# AnalogI_3_3V_LevelShift.net
KiCad netlist of a schematic drawn in EAGLE
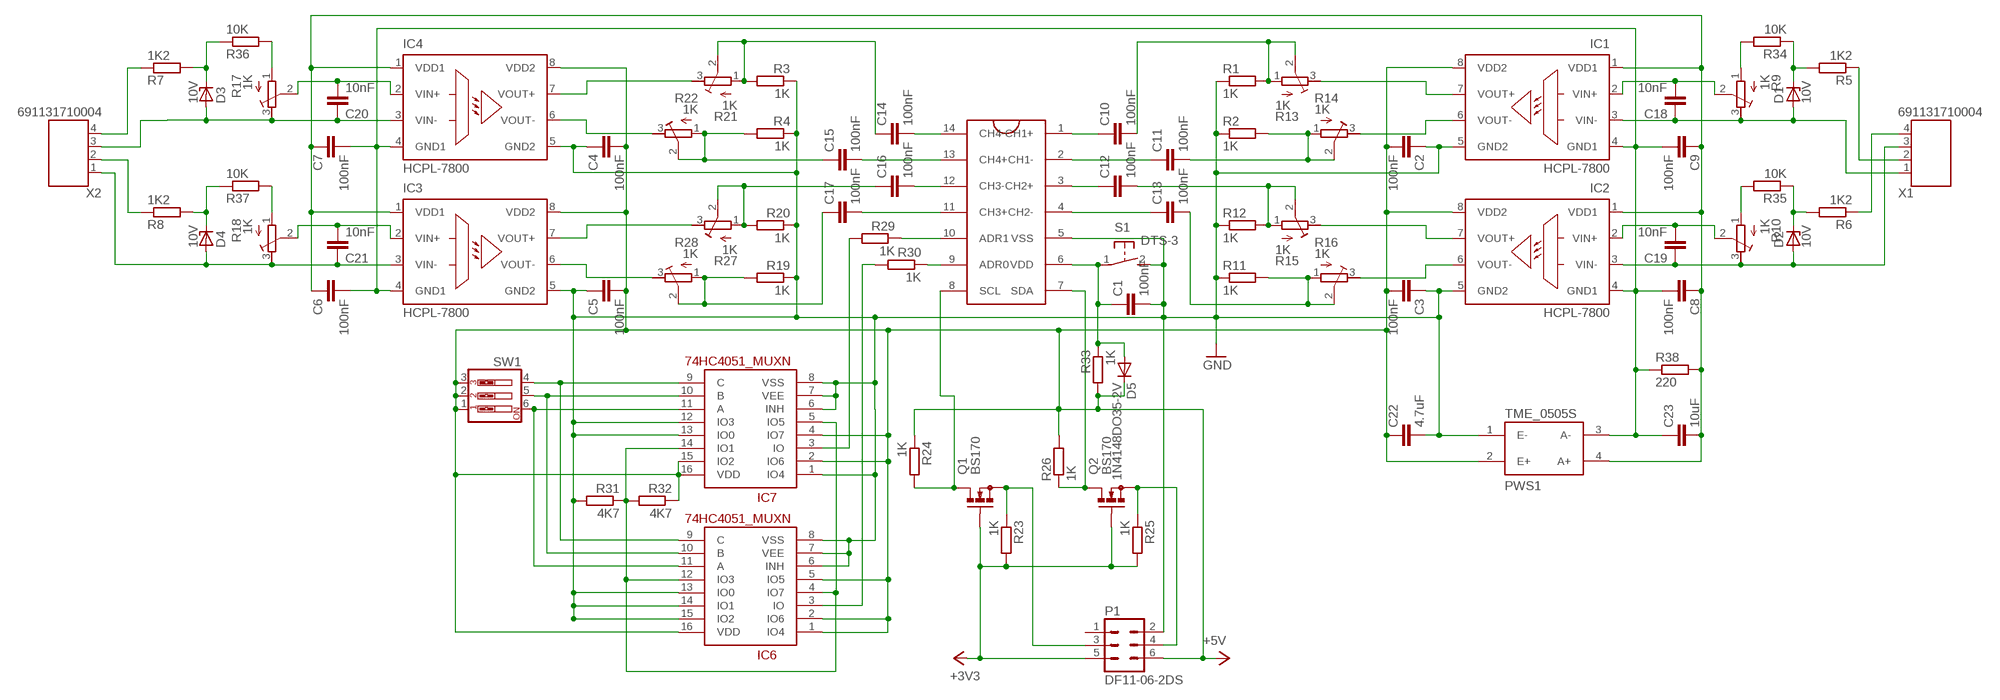
[diagram p0: schematic, sheet 1]

(export (version "E")
  (design (tool "Eeschema 10.0.6"))
  (components
    (comp (ref "C1")
      (value "100nF")
      (footprint "eagle-import:C025-024X044")
      (libsource (lib "eagle-import") (part "C-EU025-024X044"))
    )
    (comp (ref "C2")
      (value "100nF")
      (footprint "eagle-import:C025-024X044")
      (libsource (lib "eagle-import") (part "C-EU025-024X044"))
    )
    (comp (ref "C3")
      (value "100nF")
      (footprint "eagle-import:C025-024X044")
      (libsource (lib "eagle-import") (part "C-EU025-024X044"))
    )
    (comp (ref "C4")
      (value "100nF")
      (footprint "eagle-import:C025-024X044")
      (libsource (lib "eagle-import") (part "C-EU025-024X044"))
    )
    (comp (ref "C5")
      (value "100nF")
      (footprint "eagle-import:C025-024X044")
      (libsource (lib "eagle-import") (part "C-EU025-024X044"))
    )
    (comp (ref "C6")
      (value "100nF")
      (footprint "eagle-import:C025-024X044")
      (libsource (lib "eagle-import") (part "C-EU025-024X044"))
    )
    (comp (ref "C7")
      (value "100nF")
      (footprint "eagle-import:C025-024X044")
      (libsource (lib "eagle-import") (part "C-EU025-024X044"))
    )
    (comp (ref "C8")
      (value "100nF")
      (footprint "eagle-import:C025-024X044")
      (libsource (lib "eagle-import") (part "C-EU025-024X044"))
    )
    (comp (ref "C9")
      (value "100nF")
      (footprint "eagle-import:C025-024X044")
      (libsource (lib "eagle-import") (part "C-EU025-024X044"))
    )
    (comp (ref "C10")
      (value "100nF")
      (footprint "eagle-import:C5B3")
      (libsource (lib "eagle-import") (part "C5/3"))
    )
    (comp (ref "C11")
      (value "100nF")
      (footprint "eagle-import:C5B3")
      (libsource (lib "eagle-import") (part "C5/3"))
    )
    (comp (ref "C12")
      (value "100nF")
      (footprint "eagle-import:C5B3")
      (libsource (lib "eagle-import") (part "C5/3"))
    )
    (comp (ref "C13")
      (value "100nF")
      (footprint "eagle-import:C5B3")
      (libsource (lib "eagle-import") (part "C5/3"))
    )
    (comp (ref "C14")
      (value "100nF")
      (footprint "eagle-import:C5B3")
      (libsource (lib "eagle-import") (part "C5/3"))
    )
    (comp (ref "C15")
      (value "100nF")
      (footprint "eagle-import:C5B3")
      (libsource (lib "eagle-import") (part "C5/3"))
    )
    (comp (ref "C16")
      (value "100nF")
      (footprint "eagle-import:C5B3")
      (libsource (lib "eagle-import") (part "C5/3"))
    )
    (comp (ref "C17")
      (value "100nF")
      (footprint "eagle-import:C5B3")
      (libsource (lib "eagle-import") (part "C5/3"))
    )
    (comp (ref "C18")
      (value "10nF")
      (footprint "eagle-import:C2.5-3")
      (libsource (lib "eagle-import") (part "C2,5-3"))
    )
    (comp (ref "C19")
      (value "10nF")
      (footprint "eagle-import:C2.5-3")
      (libsource (lib "eagle-import") (part "C2,5-3"))
    )
    (comp (ref "C20")
      (value "10nF")
      (footprint "eagle-import:C2.5-3")
      (libsource (lib "eagle-import") (part "C2,5-3"))
    )
    (comp (ref "C21")
      (value "10nF")
      (footprint "eagle-import:C2.5-3")
      (libsource (lib "eagle-import") (part "C2,5-3"))
    )
    (comp (ref "C22")
      (value "4.7uF")
      (footprint "eagle-import:C0805")
      (libsource (lib "eagle-import") (part "C-EUC0805"))
    )
    (comp (ref "C23")
      (value "10uF")
      (footprint "eagle-import:C0805")
      (libsource (lib "eagle-import") (part "C-EUC0805"))
    )
    (comp (ref "D1")
      (value "10V")
      (footprint "eagle-import:ZDIO-2.5")
      (libsource (lib "eagle-import") (part "ZENER-DIODEZD-2.5"))
    )
    (comp (ref "D2")
      (value "10V")
      (footprint "eagle-import:ZDIO-2.5")
      (libsource (lib "eagle-import") (part "ZENER-DIODEZD-2.5"))
    )
    (comp (ref "D3")
      (value "10V")
      (footprint "eagle-import:ZDIO-2.5")
      (libsource (lib "eagle-import") (part "ZENER-DIODEZD-2.5"))
    )
    (comp (ref "D4")
      (value "10V")
      (footprint "eagle-import:ZDIO-2.5")
      (libsource (lib "eagle-import") (part "ZENER-DIODEZD-2.5"))
    )
    (comp (ref "D5")
      (value "1N4148DO35-2V")
      (footprint "eagle-import:DO35-2V")
      (libsource (lib "eagle-import") (part "1N4148DO35-2V"))
    )
    (comp (ref "IC1")
      (value "HCPL-7800")
      (footprint "eagle-import:DIL08")
      (fields (field (name "MPN") "HCPL-7800A#500"))
      (libsource (lib "eagle-import") (part "HCPL-7800"))
    )
    (comp (ref "IC2")
      (value "HCPL-7800")
      (footprint "eagle-import:DIL08")
      (fields (field (name "MPN") "HCPL-7800A#500"))
      (libsource (lib "eagle-import") (part "HCPL-7800"))
    )
    (comp (ref "IC3")
      (value "HCPL-7800")
      (footprint "eagle-import:DIL08")
      (fields (field (name "MPN") "HCPL-7800A#500"))
      (libsource (lib "eagle-import") (part "HCPL-7800"))
    )
    (comp (ref "IC4")
      (value "HCPL-7800")
      (footprint "eagle-import:DIL08")
      (fields (field (name "MPN") "HCPL-7800A#500"))
      (libsource (lib "eagle-import") (part "HCPL-7800"))
    )
    (comp (ref "IC5")
      (value "MCP3424SOIC")
      (footprint "eagle-import:14LDSOIC")
      (libsource (lib "eagle-import") (part "MCP3424SOIC"))
    )
    (comp (ref "IC6")
      (value "74HC4051_MUXN")
      (footprint "eagle-import:DIL16")
      (libsource (lib "eagle-import") (part "74HC4051_MUXN"))
    )
    (comp (ref "IC7")
      (value "74HC4051_MUXN")
      (footprint "eagle-import:DIL16")
      (libsource (lib "eagle-import") (part "74HC4051_MUXN"))
    )
    (comp (ref "P1")
      (value "DF11-06-2DS")
      (footprint "eagle-import:DF11-06DP-2DS")
      (libsource (lib "eagle-import") (part "DF11-06-2DS"))
    )
    (comp (ref "PWS1")
      (value "TME_0505S")
      (footprint "eagle-import:TMEXXXXS")
      (fields (field (name "MPN") "TME 0505S"))
      (libsource (lib "eagle-import") (part "TME_S0505"))
    )
    (comp (ref "Q1")
      (value "BS170")
      (footprint "eagle-import:SOT54E")
      (fields (field (name "MF") "ON SEMICONDUCTOR") (field (name "MPN") "BS170G"))
      (libsource (lib "eagle-import") (part "BS170"))
    )
    (comp (ref "Q2")
      (value "BS170")
      (footprint "eagle-import:SOT54E")
      (fields (field (name "MF") "ON SEMICONDUCTOR") (field (name "MPN") "BS170G"))
      (libsource (lib "eagle-import") (part "BS170"))
    )
    (comp (ref "R1")
      (value "1K")
      (footprint "eagle-import:0204V")
      (libsource (lib "eagle-import") (part "R-EU_0204/2V"))
    )
    (comp (ref "R2")
      (value "1K")
      (footprint "eagle-import:0204V")
      (libsource (lib "eagle-import") (part "R-EU_0204/2V"))
    )
    (comp (ref "R3")
      (value "1K")
      (footprint "eagle-import:0204V")
      (libsource (lib "eagle-import") (part "R-EU_0204/2V"))
    )
    (comp (ref "R4")
      (value "1K")
      (footprint "eagle-import:0204V")
      (libsource (lib "eagle-import") (part "R-EU_0204/2V"))
    )
    (comp (ref "R5")
      (value "1K2")
      (footprint "eagle-import:0204V")
      (libsource (lib "eagle-import") (part "R-EU_0204/2V"))
    )
    (comp (ref "R6")
      (value "1K2")
      (footprint "eagle-import:0204V")
      (libsource (lib "eagle-import") (part "R-EU_0204/2V"))
    )
    (comp (ref "R7")
      (value "1K2")
      (footprint "eagle-import:0204V")
      (libsource (lib "eagle-import") (part "R-EU_0204/2V"))
    )
    (comp (ref "R8")
      (value "1K2")
      (footprint "eagle-import:0204V")
      (libsource (lib "eagle-import") (part "R-EU_0204/2V"))
    )
    (comp (ref "R9")
      (value "1K")
      (footprint "eagle-import:RTRIM3296W")
      (libsource (lib "eagle-import") (part "R-TRIMM3296W"))
    )
    (comp (ref "R10")
      (value "1K")
      (footprint "eagle-import:RTRIM3296W")
      (libsource (lib "eagle-import") (part "R-TRIMM3296W"))
    )
    (comp (ref "R11")
      (value "1K")
      (footprint "eagle-import:0204V")
      (libsource (lib "eagle-import") (part "R-EU_0204/2V"))
    )
    (comp (ref "R12")
      (value "1K")
      (footprint "eagle-import:0204V")
      (libsource (lib "eagle-import") (part "R-EU_0204/2V"))
    )
    (comp (ref "R13")
      (value "1K")
      (footprint "eagle-import:RTRIM3296W")
      (libsource (lib "eagle-import") (part "R-TRIMM3296W"))
    )
    (comp (ref "R14")
      (value "1K")
      (footprint "eagle-import:RTRIM3296W")
      (libsource (lib "eagle-import") (part "R-TRIMM3296W"))
    )
    (comp (ref "R15")
      (value "1K")
      (footprint "eagle-import:RTRIM3296W")
      (libsource (lib "eagle-import") (part "R-TRIMM3296W"))
    )
    (comp (ref "R16")
      (value "1K")
      (footprint "eagle-import:RTRIM3296W")
      (libsource (lib "eagle-import") (part "R-TRIMM3296W"))
    )
    (comp (ref "R17")
      (value "1K")
      (footprint "eagle-import:RTRIM3296W")
      (libsource (lib "eagle-import") (part "R-TRIMM3296W"))
    )
    (comp (ref "R18")
      (value "1K")
      (footprint "eagle-import:RTRIM3296W")
      (libsource (lib "eagle-import") (part "R-TRIMM3296W"))
    )
    (comp (ref "R19")
      (value "1K")
      (footprint "eagle-import:0204V")
      (libsource (lib "eagle-import") (part "R-EU_0204/2V"))
    )
    (comp (ref "R20")
      (value "1K")
      (footprint "eagle-import:0204V")
      (libsource (lib "eagle-import") (part "R-EU_0204/2V"))
    )
    (comp (ref "R21")
      (value "1K")
      (footprint "eagle-import:RTRIM3296W")
      (libsource (lib "eagle-import") (part "R-TRIMM3296W"))
    )
    (comp (ref "R22")
      (value "1K")
      (footprint "eagle-import:RTRIM3296W")
      (libsource (lib "eagle-import") (part "R-TRIMM3296W"))
    )
    (comp (ref "R23")
      (value "1K")
      (footprint "eagle-import:0204V")
      (libsource (lib "eagle-import") (part "R-EU_0204/2V"))
    )
    (comp (ref "R24")
      (value "1K")
      (footprint "eagle-import:0204_5")
      (libsource (lib "eagle-import") (part "R-EU_0204/5"))
    )
    (comp (ref "R25")
      (value "1K")
      (footprint "eagle-import:0204V")
      (libsource (lib "eagle-import") (part "R-EU_0204/2V"))
    )
    (comp (ref "R26")
      (value "1K")
      (footprint "eagle-import:0204V")
      (libsource (lib "eagle-import") (part "R-EU_0204/2V"))
    )
    (comp (ref "R27")
      (value "1K")
      (footprint "eagle-import:RTRIM3296W")
      (libsource (lib "eagle-import") (part "R-TRIMM3296W"))
    )
    (comp (ref "R28")
      (value "1K")
      (footprint "eagle-import:RTRIM3296W")
      (libsource (lib "eagle-import") (part "R-TRIMM3296W"))
    )
    (comp (ref "R29")
      (value "1K")
      (footprint "eagle-import:0204_5")
      (libsource (lib "eagle-import") (part "R-EU_0204/5"))
    )
    (comp (ref "R30")
      (value "1K")
      (footprint "eagle-import:0204_5")
      (libsource (lib "eagle-import") (part "R-EU_0204/5"))
    )
    (comp (ref "R31")
      (value "4K7")
      (footprint "eagle-import:0204V")
      (libsource (lib "eagle-import") (part "R-EU_0204/2V"))
    )
    (comp (ref "R32")
      (value "4K7")
      (footprint "eagle-import:0204V")
      (libsource (lib "eagle-import") (part "R-EU_0204/2V"))
    )
    (comp (ref "R33")
      (value "1K")
      (footprint "eagle-import:0204V")
      (libsource (lib "eagle-import") (part "R-EU_0204/2V"))
    )
    (comp (ref "R34")
      (value "10K")
      (footprint "eagle-import:0204V")
      (libsource (lib "eagle-import") (part "R-EU_0204/2V"))
    )
    (comp (ref "R35")
      (value "10K")
      (footprint "eagle-import:0204V")
      (libsource (lib "eagle-import") (part "R-EU_0204/2V"))
    )
    (comp (ref "R36")
      (value "10K")
      (footprint "eagle-import:0204V")
      (libsource (lib "eagle-import") (part "R-EU_0204/2V"))
    )
    (comp (ref "R37")
      (value "10K")
      (footprint "eagle-import:0204V")
      (libsource (lib "eagle-import") (part "R-EU_0204/2V"))
    )
    (comp (ref "R38")
      (value "220")
      (footprint "eagle-import:0204V")
      (libsource (lib "eagle-import") (part "R-EU_0204/2V"))
    )
    (comp (ref "S1")
      (value "DTS-3")
      (footprint "eagle-import:DTS-3")
      (libsource (lib "eagle-import") (part "DTS-3"))
    )
    (comp (ref "SW1")
      (value "SW_DIP-3")
      (footprint "eagle-import:EDG-03")
      (libsource (lib "eagle-import") (part "SW_DIP-3"))
    )
    (comp (ref "X1")
      (value "691131710004")
      (footprint "eagle-import:691131710004")
      (libsource (lib "eagle-import") (part "691131710004"))
    )
    (comp (ref "X2")
      (value "691131710004")
      (footprint "eagle-import:691131710004")
      (libsource (lib "eagle-import") (part "691131710004"))
    )
  )
  (nets
    (net (code "1") (name "+3V3") (class "Default")
      (node (ref "P1") (pin "5") (pinfunction "5_5") (pintype "passive"))
      (node (ref "Q1") (pin "G") (pinfunction "G_G") (pintype "passive"))
      (node (ref "Q2") (pin "G") (pinfunction "G_G") (pintype "passive"))
      (node (ref "R23") (pin "2") (pinfunction "2_2") (pintype "passive"))
      (node (ref "R25") (pin "2") (pinfunction "2_2") (pintype "passive"))
    )
    (net (code "2") (name "+5V") (class "Default")
      (node (ref "C2") (pin "2") (pinfunction "2_2") (pintype "passive"))
      (node (ref "C22") (pin "1") (pinfunction "1_1") (pintype "passive"))
      (node (ref "C3") (pin "2") (pinfunction "2_2") (pintype "passive"))
      (node (ref "C4") (pin "2") (pinfunction "2_2") (pintype "passive"))
      (node (ref "C5") (pin "2") (pinfunction "2_2") (pintype "passive"))
      (node (ref "D5") (pin "C") (pinfunction "C_C") (pintype "passive"))
      (node (ref "IC1") (pin "8") (pinfunction "VDD2_8") (pintype "power_in"))
      (node (ref "IC2") (pin "8") (pinfunction "VDD2_8") (pintype "power_in"))
      (node (ref "IC3") (pin "8") (pinfunction "VDD2_8") (pintype "power_in"))
      (node (ref "IC4") (pin "8") (pinfunction "VDD2_8") (pintype "power_in"))
      (node (ref "IC6") (pin "1") (pinfunction "IO4_1") (pintype "bidirectional"))
      (node (ref "IC6") (pin "16") (pinfunction "VDD_16") (pintype "bidirectional"))
      (node (ref "IC6") (pin "2") (pinfunction "IO6_2") (pintype "bidirectional"))
      (node (ref "IC6") (pin "5") (pinfunction "IO5_5") (pintype "bidirectional"))
      (node (ref "IC7") (pin "15") (pinfunction "IO2_15") (pintype "bidirectional"))
      (node (ref "IC7") (pin "16") (pinfunction "VDD_16") (pintype "bidirectional"))
      (node (ref "IC7") (pin "2") (pinfunction "IO6_2") (pintype "bidirectional"))
      (node (ref "IC7") (pin "4") (pinfunction "IO7_4") (pintype "bidirectional"))
      (node (ref "P1") (pin "6") (pinfunction "6_6") (pintype "passive"))
      (node (ref "PWS1") (pin "2") (pinfunction "E+_2") (pintype "input"))
      (node (ref "R24") (pin "1") (pinfunction "1_1") (pintype "passive"))
      (node (ref "R26") (pin "2") (pinfunction "2_2") (pintype "passive"))
      (node (ref "R32") (pin "1") (pinfunction "1_1") (pintype "passive"))
      (node (ref "R33") (pin "2") (pinfunction "2_2") (pintype "passive"))
      (node (ref "SW1") (pin "1") (pinfunction "1_1") (pintype "passive"))
      (node (ref "SW1") (pin "2") (pinfunction "2_2") (pintype "passive"))
      (node (ref "SW1") (pin "3") (pinfunction "3_3") (pintype "passive"))
    )
    (net (code "3") (name "GND") (class "Default")
      (node (ref "C1") (pin "2") (pinfunction "2_2") (pintype "passive"))
      (node (ref "C2") (pin "1") (pinfunction "1_1") (pintype "passive"))
      (node (ref "C22") (pin "2") (pinfunction "2_2") (pintype "passive"))
      (node (ref "C3") (pin "1") (pinfunction "1_1") (pintype "passive"))
      (node (ref "C4") (pin "1") (pinfunction "1_1") (pintype "passive"))
      (node (ref "C5") (pin "1") (pinfunction "1_1") (pintype "passive"))
      (node (ref "IC1") (pin "5") (pinfunction "GND2_5") (pintype "power_in"))
      (node (ref "IC2") (pin "5") (pinfunction "GND2_5") (pintype "power_in"))
      (node (ref "IC3") (pin "5") (pinfunction "GND2_5") (pintype "power_in"))
      (node (ref "IC4") (pin "5") (pinfunction "GND2_5") (pintype "power_in"))
      (node (ref "IC5") (pin "5") (pinfunction "VSS_5") (pintype "bidirectional"))
      (node (ref "IC6") (pin "13") (pinfunction "IO0_13") (pintype "bidirectional"))
      (node (ref "IC6") (pin "14") (pinfunction "IO1_14") (pintype "bidirectional"))
      (node (ref "IC6") (pin "15") (pinfunction "IO2_15") (pintype "bidirectional"))
      (node (ref "IC6") (pin "6") (pinfunction "INH_6") (pintype "bidirectional"))
      (node (ref "IC6") (pin "7") (pinfunction "VEE_7") (pintype "bidirectional"))
      (node (ref "IC6") (pin "8") (pinfunction "VSS_8") (pintype "bidirectional"))
      (node (ref "IC7") (pin "1") (pinfunction "IO4_1") (pintype "bidirectional"))
      (node (ref "IC7") (pin "12") (pinfunction "IO3_12") (pintype "bidirectional"))
      (node (ref "IC7") (pin "13") (pinfunction "IO0_13") (pintype "bidirectional"))
      (node (ref "IC7") (pin "6") (pinfunction "INH_6") (pintype "bidirectional"))
      (node (ref "IC7") (pin "7") (pinfunction "VEE_7") (pintype "bidirectional"))
      (node (ref "IC7") (pin "8") (pinfunction "VSS_8") (pintype "bidirectional"))
      (node (ref "P1") (pin "2") (pinfunction "2_2") (pintype "passive"))
      (node (ref "PWS1") (pin "1") (pinfunction "E-_1") (pintype "input"))
      (node (ref "R1") (pin "1") (pinfunction "1_1") (pintype "passive"))
      (node (ref "R11") (pin "1") (pinfunction "1_1") (pintype "passive"))
      (node (ref "R12") (pin "1") (pinfunction "1_1") (pintype "passive"))
      (node (ref "R19") (pin "1") (pinfunction "1_1") (pintype "passive"))
      (node (ref "R2") (pin "1") (pinfunction "1_1") (pintype "passive"))
      (node (ref "R20") (pin "1") (pinfunction "1_1") (pintype "passive"))
      (node (ref "R3") (pin "1") (pinfunction "1_1") (pintype "passive"))
      (node (ref "R31") (pin "2") (pinfunction "2_2") (pintype "passive"))
      (node (ref "R4") (pin "1") (pinfunction "1_1") (pintype "passive"))
      (node (ref "S1") (pin "2") (pinfunction "2_2") (pintype "passive"))
    )
    (net (code "4") (name "Net-(D1-PadC)") (class "Default")
      (node (ref "D1") (pin "C") (pinfunction "C_C") (pintype "passive"))
      (node (ref "R34") (pin "1") (pinfunction "1_1") (pintype "passive"))
      (node (ref "R5") (pin "2") (pinfunction "2_2") (pintype "passive"))
    )
    (net (code "5") (name "Net-(D2-PadC)") (class "Default")
      (node (ref "D2") (pin "C") (pinfunction "C_C") (pintype "passive"))
      (node (ref "R35") (pin "1") (pinfunction "1_1") (pintype "passive"))
      (node (ref "R6") (pin "2") (pinfunction "2_2") (pintype "passive"))
    )
    (net (code "6") (name "Net-(D3-PadC)") (class "Default")
      (node (ref "D3") (pin "C") (pinfunction "C_C") (pintype "passive"))
      (node (ref "R36") (pin "1") (pinfunction "1_1") (pintype "passive"))
      (node (ref "R7") (pin "2") (pinfunction "2_2") (pintype "passive"))
    )
    (net (code "7") (name "Net-(D4-PadC)") (class "Default")
      (node (ref "D4") (pin "C") (pinfunction "C_C") (pintype "passive"))
      (node (ref "R37") (pin "1") (pinfunction "1_1") (pintype "passive"))
      (node (ref "R8") (pin "2") (pinfunction "2_2") (pintype "passive"))
    )
    (net (code "8") (name "Net-(IC1-GND1)") (class "Default")
      (node (ref "C23") (pin "1") (pinfunction "1_1") (pintype "passive"))
      (node (ref "C6") (pin "2") (pinfunction "2_2") (pintype "passive"))
      (node (ref "C7") (pin "2") (pinfunction "2_2") (pintype "passive"))
      (node (ref "C8") (pin "2") (pinfunction "2_2") (pintype "passive"))
      (node (ref "C9") (pin "2") (pinfunction "2_2") (pintype "passive"))
      (node (ref "IC1") (pin "4") (pinfunction "GND1_4") (pintype "power_in"))
      (node (ref "IC2") (pin "4") (pinfunction "GND1_4") (pintype "power_in"))
      (node (ref "IC3") (pin "4") (pinfunction "GND1_4") (pintype "power_in"))
      (node (ref "IC4") (pin "4") (pinfunction "GND1_4") (pintype "power_in"))
      (node (ref "PWS1") (pin "3") (pinfunction "A-_3") (pintype "output"))
      (node (ref "R38") (pin "1") (pinfunction "1_1") (pintype "passive"))
    )
    (net (code "9") (name "Net-(IC1-VDD1)") (class "Default")
      (node (ref "C23") (pin "2") (pinfunction "2_2") (pintype "passive"))
      (node (ref "C6") (pin "1") (pinfunction "1_1") (pintype "passive"))
      (node (ref "C7") (pin "1") (pinfunction "1_1") (pintype "passive"))
      (node (ref "C8") (pin "1") (pinfunction "1_1") (pintype "passive"))
      (node (ref "C9") (pin "1") (pinfunction "1_1") (pintype "passive"))
      (node (ref "IC1") (pin "1") (pinfunction "VDD1_1") (pintype "power_in"))
      (node (ref "IC2") (pin "1") (pinfunction "VDD1_1") (pintype "power_in"))
      (node (ref "IC3") (pin "1") (pinfunction "VDD1_1") (pintype "power_in"))
      (node (ref "IC4") (pin "1") (pinfunction "VDD1_1") (pintype "power_in"))
      (node (ref "PWS1") (pin "4") (pinfunction "A+_4") (pintype "output"))
      (node (ref "R38") (pin "2") (pinfunction "2_2") (pintype "passive"))
    )
    (net (code "10") (name "Net-(IC1-VIN+)") (class "Default")
      (node (ref "C18") (pin "2") (pinfunction "2_2") (pintype "passive"))
      (node (ref "IC1") (pin "2") (pinfunction "VIN+_2") (pintype "power_in"))
      (node (ref "R9") (pin "2") (pinfunction "S_2") (pintype "passive"))
    )
    (net (code "11") (name "Net-(IC1-VIN-)") (class "Default")
      (node (ref "C18") (pin "1") (pinfunction "1_1") (pintype "passive"))
      (node (ref "D1") (pin "A") (pinfunction "A_A") (pintype "passive"))
      (node (ref "IC1") (pin "3") (pinfunction "VIN-_3") (pintype "power_in"))
      (node (ref "R9") (pin "3") (pinfunction "E_3") (pintype "passive"))
      (node (ref "X1") (pin "1") (pinfunction "1_1") (pintype "passive"))
    )
    (net (code "12") (name "Net-(IC1-VOUT+)") (class "Default")
      (node (ref "IC1") (pin "7") (pinfunction "VOUT+_7") (pintype "power_in"))
      (node (ref "R13") (pin "3") (pinfunction "E_3") (pintype "passive"))
    )
    (net (code "13") (name "Net-(IC1-VOUT-)") (class "Default")
      (node (ref "IC1") (pin "6") (pinfunction "VOUT-_6") (pintype "power_in"))
      (node (ref "R14") (pin "3") (pinfunction "E_3") (pintype "passive"))
    )
    (net (code "14") (name "Net-(IC2-VIN+)") (class "Default")
      (node (ref "C19") (pin "2") (pinfunction "2_2") (pintype "passive"))
      (node (ref "IC2") (pin "2") (pinfunction "VIN+_2") (pintype "power_in"))
      (node (ref "R10") (pin "2") (pinfunction "S_2") (pintype "passive"))
    )
    (net (code "15") (name "Net-(IC2-VIN-)") (class "Default")
      (node (ref "C19") (pin "1") (pinfunction "1_1") (pintype "passive"))
      (node (ref "D2") (pin "A") (pinfunction "A_A") (pintype "passive"))
      (node (ref "IC2") (pin "3") (pinfunction "VIN-_3") (pintype "power_in"))
      (node (ref "R10") (pin "3") (pinfunction "E_3") (pintype "passive"))
      (node (ref "X1") (pin "3") (pinfunction "3_3") (pintype "passive"))
    )
    (net (code "16") (name "Net-(IC2-VOUT+)") (class "Default")
      (node (ref "IC2") (pin "7") (pinfunction "VOUT+_7") (pintype "power_in"))
      (node (ref "R15") (pin "3") (pinfunction "E_3") (pintype "passive"))
    )
    (net (code "17") (name "Net-(IC2-VOUT-)") (class "Default")
      (node (ref "IC2") (pin "6") (pinfunction "VOUT-_6") (pintype "power_in"))
      (node (ref "R16") (pin "3") (pinfunction "E_3") (pintype "passive"))
    )
    (net (code "18") (name "Net-(IC3-VIN+)") (class "Default")
      (node (ref "C21") (pin "2") (pinfunction "2_2") (pintype "passive"))
      (node (ref "IC3") (pin "2") (pinfunction "VIN+_2") (pintype "power_in"))
      (node (ref "R18") (pin "2") (pinfunction "S_2") (pintype "passive"))
    )
    (net (code "19") (name "Net-(IC3-VIN-)") (class "Default")
      (node (ref "C21") (pin "1") (pinfunction "1_1") (pintype "passive"))
      (node (ref "D4") (pin "A") (pinfunction "A_A") (pintype "passive"))
      (node (ref "IC3") (pin "3") (pinfunction "VIN-_3") (pintype "power_in"))
      (node (ref "R18") (pin "3") (pinfunction "E_3") (pintype "passive"))
      (node (ref "X2") (pin "1") (pinfunction "1_1") (pintype "passive"))
    )
    (net (code "20") (name "Net-(IC3-VOUT+)") (class "Default")
      (node (ref "IC3") (pin "7") (pinfunction "VOUT+_7") (pintype "power_in"))
      (node (ref "R27") (pin "3") (pinfunction "E_3") (pintype "passive"))
    )
    (net (code "21") (name "Net-(IC3-VOUT-)") (class "Default")
      (node (ref "IC3") (pin "6") (pinfunction "VOUT-_6") (pintype "power_in"))
      (node (ref "R28") (pin "3") (pinfunction "E_3") (pintype "passive"))
    )
    (net (code "22") (name "Net-(IC4-VIN+)") (class "Default")
      (node (ref "C20") (pin "2") (pinfunction "2_2") (pintype "passive"))
      (node (ref "IC4") (pin "2") (pinfunction "VIN+_2") (pintype "power_in"))
      (node (ref "R17") (pin "2") (pinfunction "S_2") (pintype "passive"))
    )
    (net (code "23") (name "Net-(IC4-VIN-)") (class "Default")
      (node (ref "C20") (pin "1") (pinfunction "1_1") (pintype "passive"))
      (node (ref "D3") (pin "A") (pinfunction "A_A") (pintype "passive"))
      (node (ref "IC4") (pin "3") (pinfunction "VIN-_3") (pintype "power_in"))
      (node (ref "R17") (pin "3") (pinfunction "E_3") (pintype "passive"))
      (node (ref "X2") (pin "3") (pinfunction "3_3") (pintype "passive"))
    )
    (net (code "24") (name "Net-(IC4-VOUT+)") (class "Default")
      (node (ref "IC4") (pin "7") (pinfunction "VOUT+_7") (pintype "power_in"))
      (node (ref "R21") (pin "3") (pinfunction "E_3") (pintype "passive"))
    )
    (net (code "25") (name "Net-(IC4-VOUT-)") (class "Default")
      (node (ref "IC4") (pin "6") (pinfunction "VOUT-_6") (pintype "power_in"))
      (node (ref "R22") (pin "3") (pinfunction "E_3") (pintype "passive"))
    )
    (net (code "26") (name "Net-(IC5-ADR0)") (class "Default")
      (node (ref "IC5") (pin "9") (pinfunction "ADR0_9") (pintype "bidirectional"))
      (node (ref "R30") (pin "1") (pinfunction "1_1") (pintype "passive"))
    )
    (net (code "27") (name "Net-(IC5-ADR1)") (class "Default")
      (node (ref "IC5") (pin "10") (pinfunction "ADR1_10") (pintype "bidirectional"))
      (node (ref "R29") (pin "1") (pinfunction "1_1") (pintype "passive"))
    )
    (net (code "28") (name "Net-(IC5-CH1+)") (class "Default")
      (node (ref "C10") (pin "1") (pinfunction "1_1") (pintype "passive"))
      (node (ref "IC5") (pin "1") (pinfunction "CH1+_1") (pintype "bidirectional"))
    )
    (net (code "29") (name "Net-(IC5-CH1-)") (class "Default")
      (node (ref "C11") (pin "1") (pinfunction "1_1") (pintype "passive"))
      (node (ref "IC5") (pin "2") (pinfunction "CH1-_2") (pintype "bidirectional"))
    )
    (net (code "30") (name "Net-(IC5-CH2+)") (class "Default")
      (node (ref "C12") (pin "1") (pinfunction "1_1") (pintype "passive"))
      (node (ref "IC5") (pin "3") (pinfunction "CH2+_3") (pintype "bidirectional"))
    )
    (net (code "31") (name "Net-(IC5-CH2-)") (class "Default")
      (node (ref "C13") (pin "1") (pinfunction "1_1") (pintype "passive"))
      (node (ref "IC5") (pin "4") (pinfunction "CH2-_4") (pintype "bidirectional"))
    )
    (net (code "32") (name "Net-(IC5-CH3+)") (class "Default")
      (node (ref "C17") (pin "2") (pinfunction "2_2") (pintype "passive"))
      (node (ref "IC5") (pin "11") (pinfunction "CH3+_11") (pintype "bidirectional"))
    )
    (net (code "33") (name "Net-(IC5-CH3-)") (class "Default")
      (node (ref "C16") (pin "2") (pinfunction "2_2") (pintype "passive"))
      (node (ref "IC5") (pin "12") (pinfunction "CH3-_12") (pintype "bidirectional"))
    )
    (net (code "34") (name "Net-(IC5-CH4+)") (class "Default")
      (node (ref "C15") (pin "2") (pinfunction "2_2") (pintype "passive"))
      (node (ref "IC5") (pin "13") (pinfunction "CH4+_13") (pintype "bidirectional"))
    )
    (net (code "35") (name "Net-(IC5-CH4-)") (class "Default")
      (node (ref "C14") (pin "2") (pinfunction "2_2") (pintype "passive"))
      (node (ref "IC5") (pin "14") (pinfunction "CH4-_14") (pintype "bidirectional"))
    )
    (net (code "36") (name "Net-(IC5-SCL)") (class "Default")
      (node (ref "IC5") (pin "8") (pinfunction "SCL_8") (pintype "bidirectional"))
      (node (ref "Q1") (pin "D") (pinfunction "D_D") (pintype "passive"))
      (node (ref "R24") (pin "2") (pinfunction "2_2") (pintype "passive"))
    )
    (net (code "37") (name "Net-(IC5-SDA)") (class "Default")
      (node (ref "IC5") (pin "7") (pinfunction "SDA_7") (pintype "bidirectional"))
      (node (ref "Q2") (pin "D") (pinfunction "D_D") (pintype "passive"))
      (node (ref "R26") (pin "1") (pinfunction "1_1") (pintype "passive"))
    )
    (net (code "38") (name "Net-(IC5-VDD)") (class "Default")
      (node (ref "C1") (pin "1") (pinfunction "1_1") (pintype "passive"))
      (node (ref "D5") (pin "A") (pinfunction "A_A") (pintype "passive"))
      (node (ref "IC5") (pin "6") (pinfunction "VDD_6") (pintype "bidirectional"))
      (node (ref "R33") (pin "1") (pinfunction "1_1") (pintype "passive"))
      (node (ref "S1") (pin "1") (pinfunction "1_1") (pintype "passive"))
    )
    (net (code "39") (name "Net-(IC6-A)") (class "Default")
      (node (ref "IC6") (pin "11") (pinfunction "A_11") (pintype "bidirectional"))
      (node (ref "IC7") (pin "11") (pinfunction "A_11") (pintype "bidirectional"))
      (node (ref "SW1") (pin "6") (pinfunction "6_6") (pintype "passive"))
    )
    (net (code "40") (name "Net-(IC6-B)") (class "Default")
      (node (ref "IC6") (pin "10") (pinfunction "B_10") (pintype "bidirectional"))
      (node (ref "IC7") (pin "10") (pinfunction "B_10") (pintype "bidirectional"))
      (node (ref "SW1") (pin "5") (pinfunction "5_5") (pintype "passive"))
    )
    (net (code "41") (name "Net-(IC6-C)") (class "Default")
      (node (ref "IC6") (pin "9") (pinfunction "C_9") (pintype "bidirectional"))
      (node (ref "IC7") (pin "9") (pinfunction "C_9") (pintype "bidirectional"))
      (node (ref "SW1") (pin "4") (pinfunction "4_4") (pintype "passive"))
    )
    (net (code "42") (name "Net-(IC6-IO)") (class "Default")
      (node (ref "IC6") (pin "3") (pinfunction "IO_3") (pintype "bidirectional"))
      (node (ref "R30") (pin "2") (pinfunction "2_2") (pintype "passive"))
    )
    (net (code "43") (name "Net-(IC6-IO3)") (class "Default")
      (node (ref "IC6") (pin "12") (pinfunction "IO3_12") (pintype "bidirectional"))
      (node (ref "IC6") (pin "4") (pinfunction "IO7_4") (pintype "bidirectional"))
      (node (ref "IC7") (pin "14") (pinfunction "IO1_14") (pintype "bidirectional"))
      (node (ref "IC7") (pin "5") (pinfunction "IO5_5") (pintype "bidirectional"))
      (node (ref "R31") (pin "1") (pinfunction "1_1") (pintype "passive"))
      (node (ref "R32") (pin "2") (pinfunction "2_2") (pintype "passive"))
    )
    (net (code "44") (name "Net-(IC7-IO)") (class "Default")
      (node (ref "IC7") (pin "3") (pinfunction "IO_3") (pintype "bidirectional"))
      (node (ref "R29") (pin "2") (pinfunction "2_2") (pintype "passive"))
    )
    (net (code "45") (name "Net-(P1-Pad3)") (class "Default")
      (node (ref "P1") (pin "3") (pinfunction "3_3") (pintype "passive"))
      (node (ref "Q1") (pin "S") (pinfunction "S_S") (pintype "passive"))
      (node (ref "R23") (pin "1") (pinfunction "1_1") (pintype "passive"))
    )
    (net (code "46") (name "Net-(P1-Pad4)") (class "Default")
      (node (ref "P1") (pin "4") (pinfunction "4_4") (pintype "passive"))
      (node (ref "Q2") (pin "S") (pinfunction "S_S") (pintype "passive"))
      (node (ref "R25") (pin "1") (pinfunction "1_1") (pintype "passive"))
    )
    (net (code "47") (name "Net-(R5-Pad1)") (class "Default")
      (node (ref "R5") (pin "1") (pinfunction "1_1") (pintype "passive"))
      (node (ref "X1") (pin "2") (pinfunction "2_2") (pintype "passive"))
    )
    (net (code "48") (name "Net-(R6-Pad1)") (class "Default")
      (node (ref "R6") (pin "1") (pinfunction "1_1") (pintype "passive"))
      (node (ref "X1") (pin "4") (pinfunction "4_4") (pintype "passive"))
    )
    (net (code "49") (name "Net-(R7-Pad1)") (class "Default")
      (node (ref "R7") (pin "1") (pinfunction "1_1") (pintype "passive"))
      (node (ref "X2") (pin "4") (pinfunction "4_4") (pintype "passive"))
    )
    (net (code "50") (name "Net-(R8-Pad1)") (class "Default")
      (node (ref "R8") (pin "1") (pinfunction "1_1") (pintype "passive"))
      (node (ref "X2") (pin "2") (pinfunction "2_2") (pintype "passive"))
    )
    (net (code "51") (name "Net-(R9-A)") (class "Default")
      (node (ref "R34") (pin "2") (pinfunction "2_2") (pintype "passive"))
      (node (ref "R9") (pin "1") (pinfunction "A_1") (pintype "passive"))
    )
    (net (code "52") (name "Net-(R10-A)") (class "Default")
      (node (ref "R10") (pin "1") (pinfunction "A_1") (pintype "passive"))
      (node (ref "R35") (pin "2") (pinfunction "2_2") (pintype "passive"))
    )
    (net (code "53") (name "Net-(R13-A)") (class "Default")
      (node (ref "C10") (pin "2") (pinfunction "2_2") (pintype "passive"))
      (node (ref "R1") (pin "2") (pinfunction "2_2") (pintype "passive"))
      (node (ref "R13") (pin "1") (pinfunction "A_1") (pintype "passive"))
      (node (ref "R13") (pin "2") (pinfunction "S_2") (pintype "passive"))
    )
    (net (code "54") (name "Net-(R14-A)") (class "Default")
      (node (ref "C11") (pin "2") (pinfunction "2_2") (pintype "passive"))
      (node (ref "R14") (pin "1") (pinfunction "A_1") (pintype "passive"))
      (node (ref "R14") (pin "2") (pinfunction "S_2") (pintype "passive"))
      (node (ref "R2") (pin "2") (pinfunction "2_2") (pintype "passive"))
    )
    (net (code "55") (name "Net-(R15-A)") (class "Default")
      (node (ref "C12") (pin "2") (pinfunction "2_2") (pintype "passive"))
      (node (ref "R12") (pin "2") (pinfunction "2_2") (pintype "passive"))
      (node (ref "R15") (pin "1") (pinfunction "A_1") (pintype "passive"))
      (node (ref "R15") (pin "2") (pinfunction "S_2") (pintype "passive"))
    )
    (net (code "56") (name "Net-(R16-A)") (class "Default")
      (node (ref "C13") (pin "2") (pinfunction "2_2") (pintype "passive"))
      (node (ref "R11") (pin "2") (pinfunction "2_2") (pintype "passive"))
      (node (ref "R16") (pin "1") (pinfunction "A_1") (pintype "passive"))
      (node (ref "R16") (pin "2") (pinfunction "S_2") (pintype "passive"))
    )
    (net (code "57") (name "Net-(R17-A)") (class "Default")
      (node (ref "R17") (pin "1") (pinfunction "A_1") (pintype "passive"))
      (node (ref "R36") (pin "2") (pinfunction "2_2") (pintype "passive"))
    )
    (net (code "58") (name "Net-(R18-A)") (class "Default")
      (node (ref "R18") (pin "1") (pinfunction "A_1") (pintype "passive"))
      (node (ref "R37") (pin "2") (pinfunction "2_2") (pintype "passive"))
    )
    (net (code "59") (name "Net-(R21-A)") (class "Default")
      (node (ref "C14") (pin "1") (pinfunction "1_1") (pintype "passive"))
      (node (ref "R21") (pin "1") (pinfunction "A_1") (pintype "passive"))
      (node (ref "R21") (pin "2") (pinfunction "S_2") (pintype "passive"))
      (node (ref "R3") (pin "2") (pinfunction "2_2") (pintype "passive"))
    )
    (net (code "60") (name "Net-(R22-A)") (class "Default")
      (node (ref "C15") (pin "1") (pinfunction "1_1") (pintype "passive"))
      (node (ref "R22") (pin "1") (pinfunction "A_1") (pintype "passive"))
      (node (ref "R22") (pin "2") (pinfunction "S_2") (pintype "passive"))
      (node (ref "R4") (pin "2") (pinfunction "2_2") (pintype "passive"))
    )
    (net (code "61") (name "Net-(R27-A)") (class "Default")
      (node (ref "C16") (pin "1") (pinfunction "1_1") (pintype "passive"))
      (node (ref "R20") (pin "2") (pinfunction "2_2") (pintype "passive"))
      (node (ref "R27") (pin "1") (pinfunction "A_1") (pintype "passive"))
      (node (ref "R27") (pin "2") (pinfunction "S_2") (pintype "passive"))
    )
    (net (code "62") (name "Net-(R28-A)") (class "Default")
      (node (ref "C17") (pin "1") (pinfunction "1_1") (pintype "passive"))
      (node (ref "R19") (pin "2") (pinfunction "2_2") (pintype "passive"))
      (node (ref "R28") (pin "1") (pinfunction "A_1") (pintype "passive"))
      (node (ref "R28") (pin "2") (pinfunction "S_2") (pintype "passive"))
    )
    (net (code "63") (name "unconnected-(P1-Pad1)") (class "Default")
      (node (ref "P1") (pin "1") (pinfunction "1_1") (pintype "passive"))
    )
  )
)
